# USB_5Vswitch.net
KiCad netlist of a schematic drawn in EAGLE
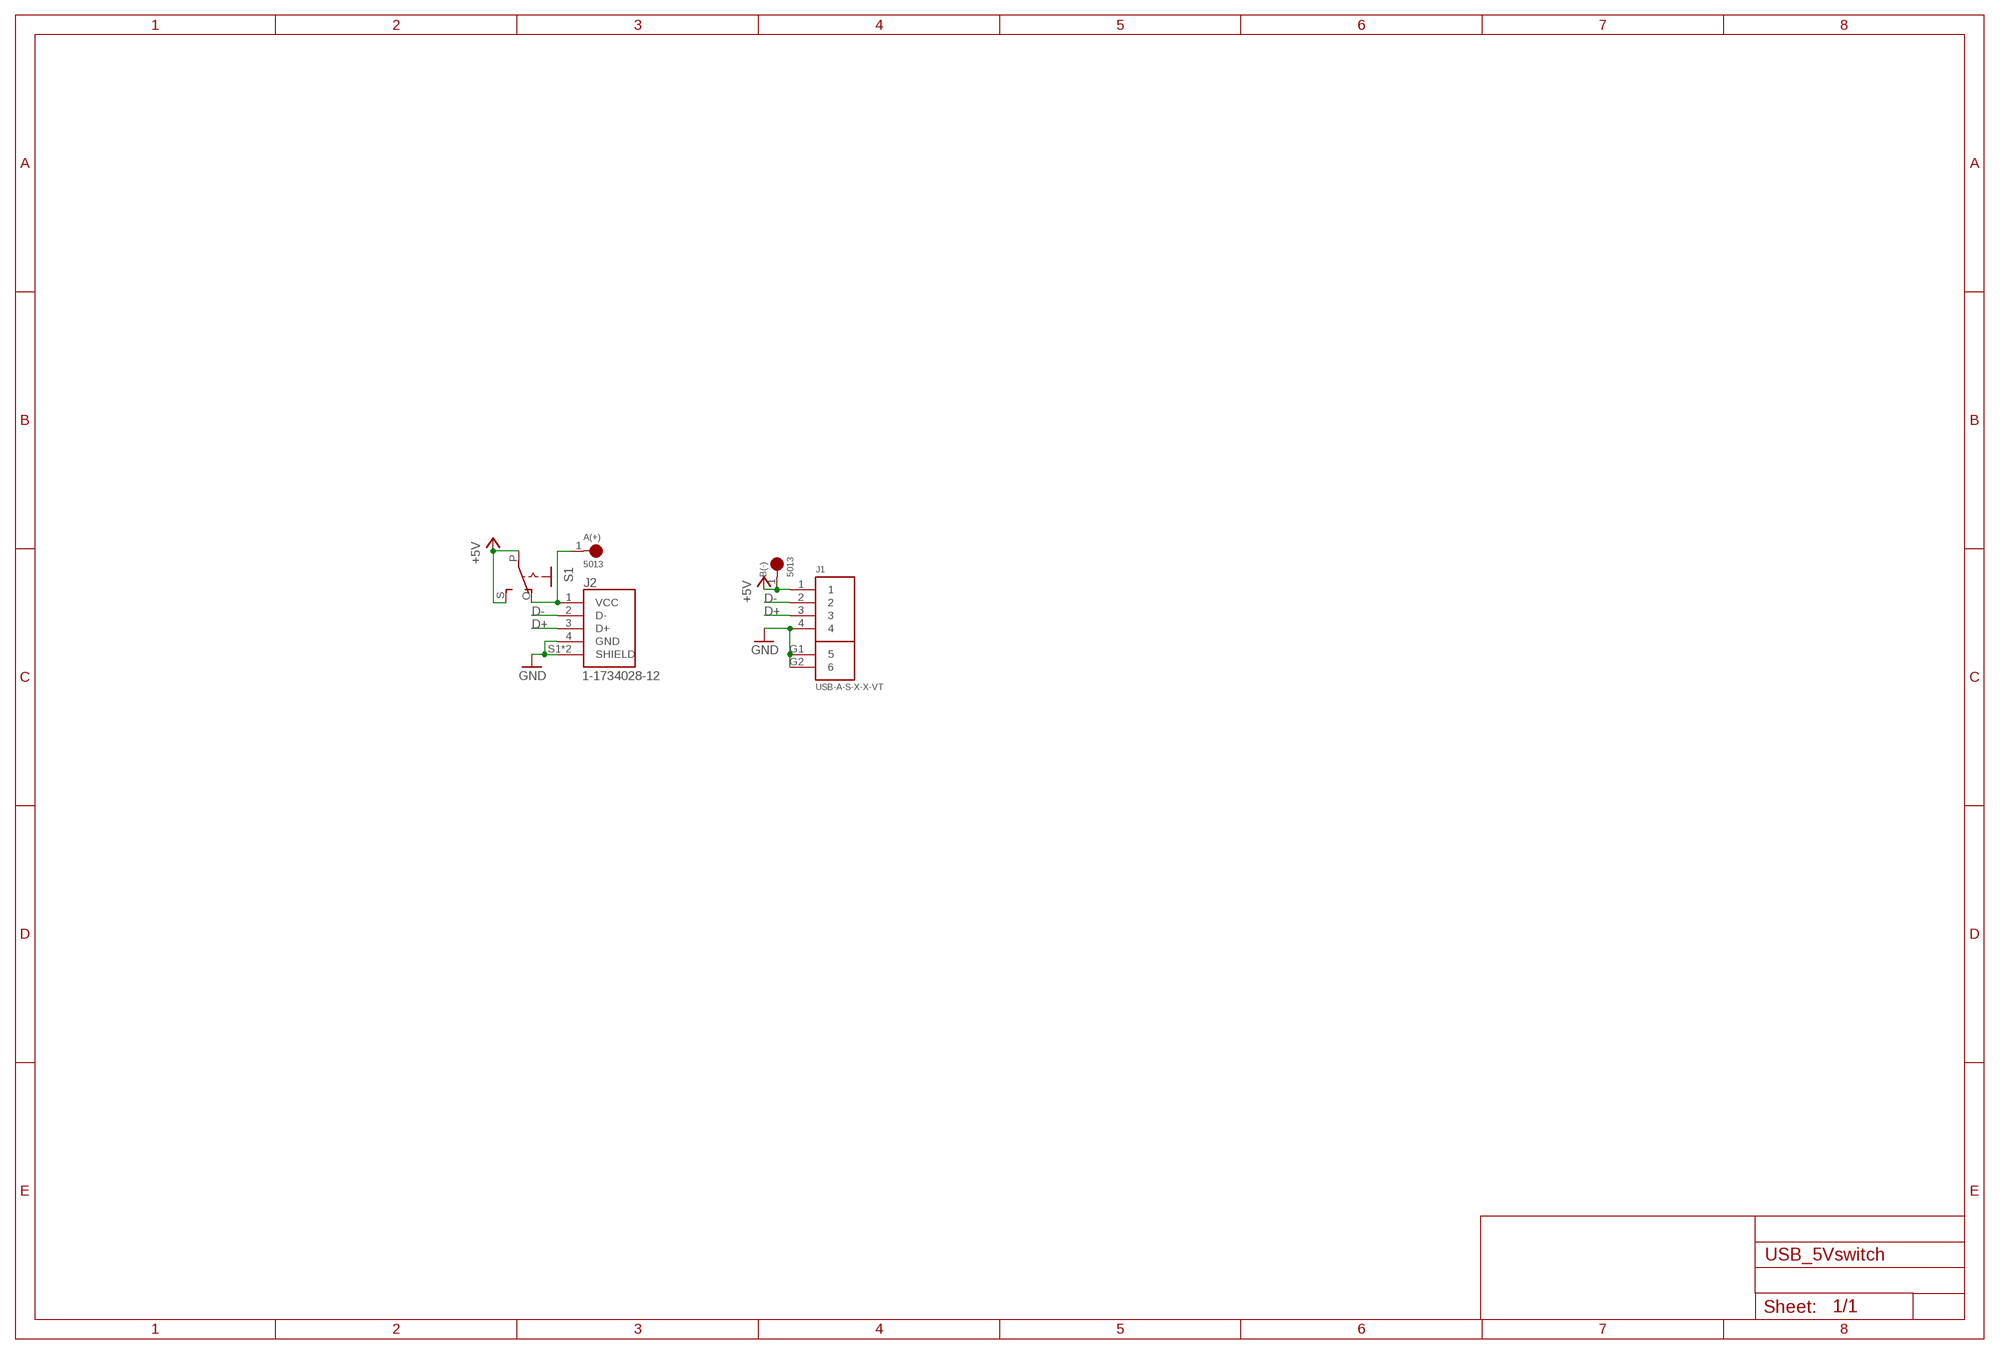
[diagram p0: schematic, sheet 1]

(export (version "E")
  (design (tool "Eeschema 10.0.6"))
  (components
    (comp (ref "A(+)")
      (value "5013")
      (footprint "eagle-import:TESTPOINT_5013")
      (fields (field (name "MF") "Keystone Electronics"))
      (libsource (lib "eagle-import") (part "5013"))
    )
    (comp (ref "B(-)")
      (value "5013")
      (footprint "eagle-import:TESTPOINT_5013")
      (fields (field (name "MF") "Keystone Electronics"))
      (libsource (lib "eagle-import") (part "5013"))
    )
    (comp (ref "J1")
      (value "USB-A-S-X-X-VT")
      (footprint "eagle-import:USB-A-S-X-X-VT")
      (fields (field (name "MF") "Samtec") (field (name "MP") "USB-A-S-S-W-VT"))
      (libsource (lib "eagle-import") (part "USB-A-S-X-X-VT"))
    )
    (comp (ref "J2")
      (value "1-1734028-12")
      (footprint "eagle-import:TE_1-1734028-2")
      (libsource (lib "eagle-import") (part "1-1734028-12"))
    )
    (comp (ref "S1")
      (value "EG1218S")
      (footprint "eagle-import:EG1218")
      (libsource (lib "eagle-import") (part "EG1218S"))
    )
  )
  (nets
    (net (code "1") (name "+5V") (class "Default")
      (node (ref "B(-)") (pin "1") (pinfunction "TP_1") (pintype "passive"))
      (node (ref "J1") (pin "1") (pinfunction "1_1") (pintype "bidirectional"))
      (node (ref "S1") (pin "P") (pinfunction "P_P") (pintype "passive"))
      (node (ref "S1") (pin "S") (pinfunction "S_S") (pintype "passive"))
    )
    (net (code "2") (name "/D+") (class "Default")
      (node (ref "J1") (pin "3") (pinfunction "3_3") (pintype "bidirectional"))
      (node (ref "J2") (pin "3") (pinfunction "D+_3") (pintype "bidirectional"))
    )
    (net (code "3") (name "/D-") (class "Default")
      (node (ref "J1") (pin "2") (pinfunction "2_2") (pintype "bidirectional"))
      (node (ref "J2") (pin "2") (pinfunction "D-_2") (pintype "bidirectional"))
    )
    (net (code "4") (name "GND") (class "Default")
      (node (ref "J1") (pin "4") (pinfunction "4_4") (pintype "bidirectional"))
      (node (ref "J1") (pin "G1") (pinfunction "5_G1") (pintype "bidirectional"))
      (node (ref "J1") (pin "G2") (pinfunction "6_G2") (pintype "bidirectional"))
      (node (ref "J2") (pin "4") (pinfunction "GND_4") (pintype "power_in"))
      (node (ref "J2") (pin "S1") (pinfunction "SHIELD_S1") (pintype "power_in"))
      (node (ref "J2") (pin "S2") (pinfunction "SHIELD_S2") (pintype "power_in"))
    )
    (net (code "5") (name "Net-(A(+)-TP)") (class "Default")
      (node (ref "A(+)") (pin "1") (pinfunction "TP_1") (pintype "passive"))
      (node (ref "J2") (pin "1") (pinfunction "VCC_1") (pintype "power_in"))
      (node (ref "S1") (pin "O") (pinfunction "O_O") (pintype "passive"))
    )
  )
)
